# question_2.net
KiCad netlist of a schematic drawn in EAGLE
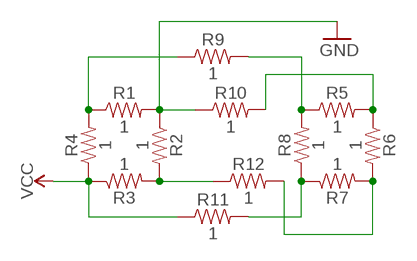
[diagram p0: schematic, sheet 1]

(export (version "E")
  (design (tool "Eeschema 10.0.6"))
  (components
    (comp (ref "R1")
      (value "1")
      (footprint "eagle-import:0603")
      (libsource (lib "eagle-import") (part "1OHM-0603-1/10W-1%"))
    )
    (comp (ref "R2")
      (value "1")
      (footprint "eagle-import:0603")
      (libsource (lib "eagle-import") (part "1OHM-0603-1/10W-1%"))
    )
    (comp (ref "R3")
      (value "1")
      (footprint "eagle-import:0603")
      (libsource (lib "eagle-import") (part "1OHM-0603-1/10W-1%"))
    )
    (comp (ref "R4")
      (value "1")
      (footprint "eagle-import:0603")
      (libsource (lib "eagle-import") (part "1OHM-0603-1/10W-1%"))
    )
    (comp (ref "R5")
      (value "1")
      (footprint "eagle-import:0603")
      (libsource (lib "eagle-import") (part "1OHM-0603-1/10W-1%"))
    )
    (comp (ref "R6")
      (value "1")
      (footprint "eagle-import:0603")
      (libsource (lib "eagle-import") (part "1OHM-0603-1/10W-1%"))
    )
    (comp (ref "R7")
      (value "1")
      (footprint "eagle-import:0603")
      (libsource (lib "eagle-import") (part "1OHM-0603-1/10W-1%"))
    )
    (comp (ref "R8")
      (value "1")
      (footprint "eagle-import:0603")
      (libsource (lib "eagle-import") (part "1OHM-0603-1/10W-1%"))
    )
    (comp (ref "R9")
      (value "1")
      (footprint "eagle-import:0603")
      (libsource (lib "eagle-import") (part "1OHM-0603-1/10W-1%"))
    )
    (comp (ref "R10")
      (value "1")
      (footprint "eagle-import:0603")
      (libsource (lib "eagle-import") (part "1OHM-0603-1/10W-1%"))
    )
    (comp (ref "R11")
      (value "1")
      (footprint "eagle-import:0603")
      (libsource (lib "eagle-import") (part "1OHM-0603-1/10W-1%"))
    )
    (comp (ref "R12")
      (value "1")
      (footprint "eagle-import:0603")
      (libsource (lib "eagle-import") (part "1OHM-0603-1/10W-1%"))
    )
  )
  (nets
    (net (code "1") (name "GND") (class "Default")
      (node (ref "R1") (pin "2") (pinfunction "2_2") (pintype "passive"))
      (node (ref "R10") (pin "1") (pinfunction "1_1") (pintype "passive"))
      (node (ref "R2") (pin "1") (pinfunction "1_1") (pintype "passive"))
    )
    (net (code "2") (name "Net-(R1-Pad1)") (class "Default")
      (node (ref "R1") (pin "1") (pinfunction "1_1") (pintype "passive"))
      (node (ref "R4") (pin "2") (pinfunction "2_2") (pintype "passive"))
      (node (ref "R9") (pin "1") (pinfunction "1_1") (pintype "passive"))
    )
    (net (code "3") (name "Net-(R5-Pad1)") (class "Default")
      (node (ref "R5") (pin "1") (pinfunction "1_1") (pintype "passive"))
      (node (ref "R8") (pin "2") (pinfunction "2_2") (pintype "passive"))
      (node (ref "R9") (pin "2") (pinfunction "2_2") (pintype "passive"))
    )
    (net (code "4") (name "Net-(R10-Pad2)") (class "Default")
      (node (ref "R10") (pin "2") (pinfunction "2_2") (pintype "passive"))
      (node (ref "R5") (pin "2") (pinfunction "2_2") (pintype "passive"))
      (node (ref "R6") (pin "1") (pinfunction "1_1") (pintype "passive"))
    )
    (net (code "5") (name "Net-(R11-Pad2)") (class "Default")
      (node (ref "R11") (pin "2") (pinfunction "2_2") (pintype "passive"))
      (node (ref "R7") (pin "1") (pinfunction "1_1") (pintype "passive"))
      (node (ref "R8") (pin "1") (pinfunction "1_1") (pintype "passive"))
    )
    (net (code "6") (name "Net-(R12-Pad1)") (class "Default")
      (node (ref "R12") (pin "1") (pinfunction "1_1") (pintype "passive"))
      (node (ref "R2") (pin "2") (pinfunction "2_2") (pintype "passive"))
      (node (ref "R3") (pin "2") (pinfunction "2_2") (pintype "passive"))
    )
    (net (code "7") (name "Net-(R12-Pad2)") (class "Default")
      (node (ref "R12") (pin "2") (pinfunction "2_2") (pintype "passive"))
      (node (ref "R6") (pin "2") (pinfunction "2_2") (pintype "passive"))
      (node (ref "R7") (pin "2") (pinfunction "2_2") (pintype "passive"))
    )
    (net (code "8") (name "VCC") (class "Default")
      (node (ref "R11") (pin "1") (pinfunction "1_1") (pintype "passive"))
      (node (ref "R3") (pin "1") (pinfunction "1_1") (pintype "passive"))
      (node (ref "R4") (pin "1") (pinfunction "1_1") (pintype "passive"))
    )
  )
)
